# 1-Schematic_LEDmatrix.net
KiCad netlist of a schematic drawn in EasyEDA
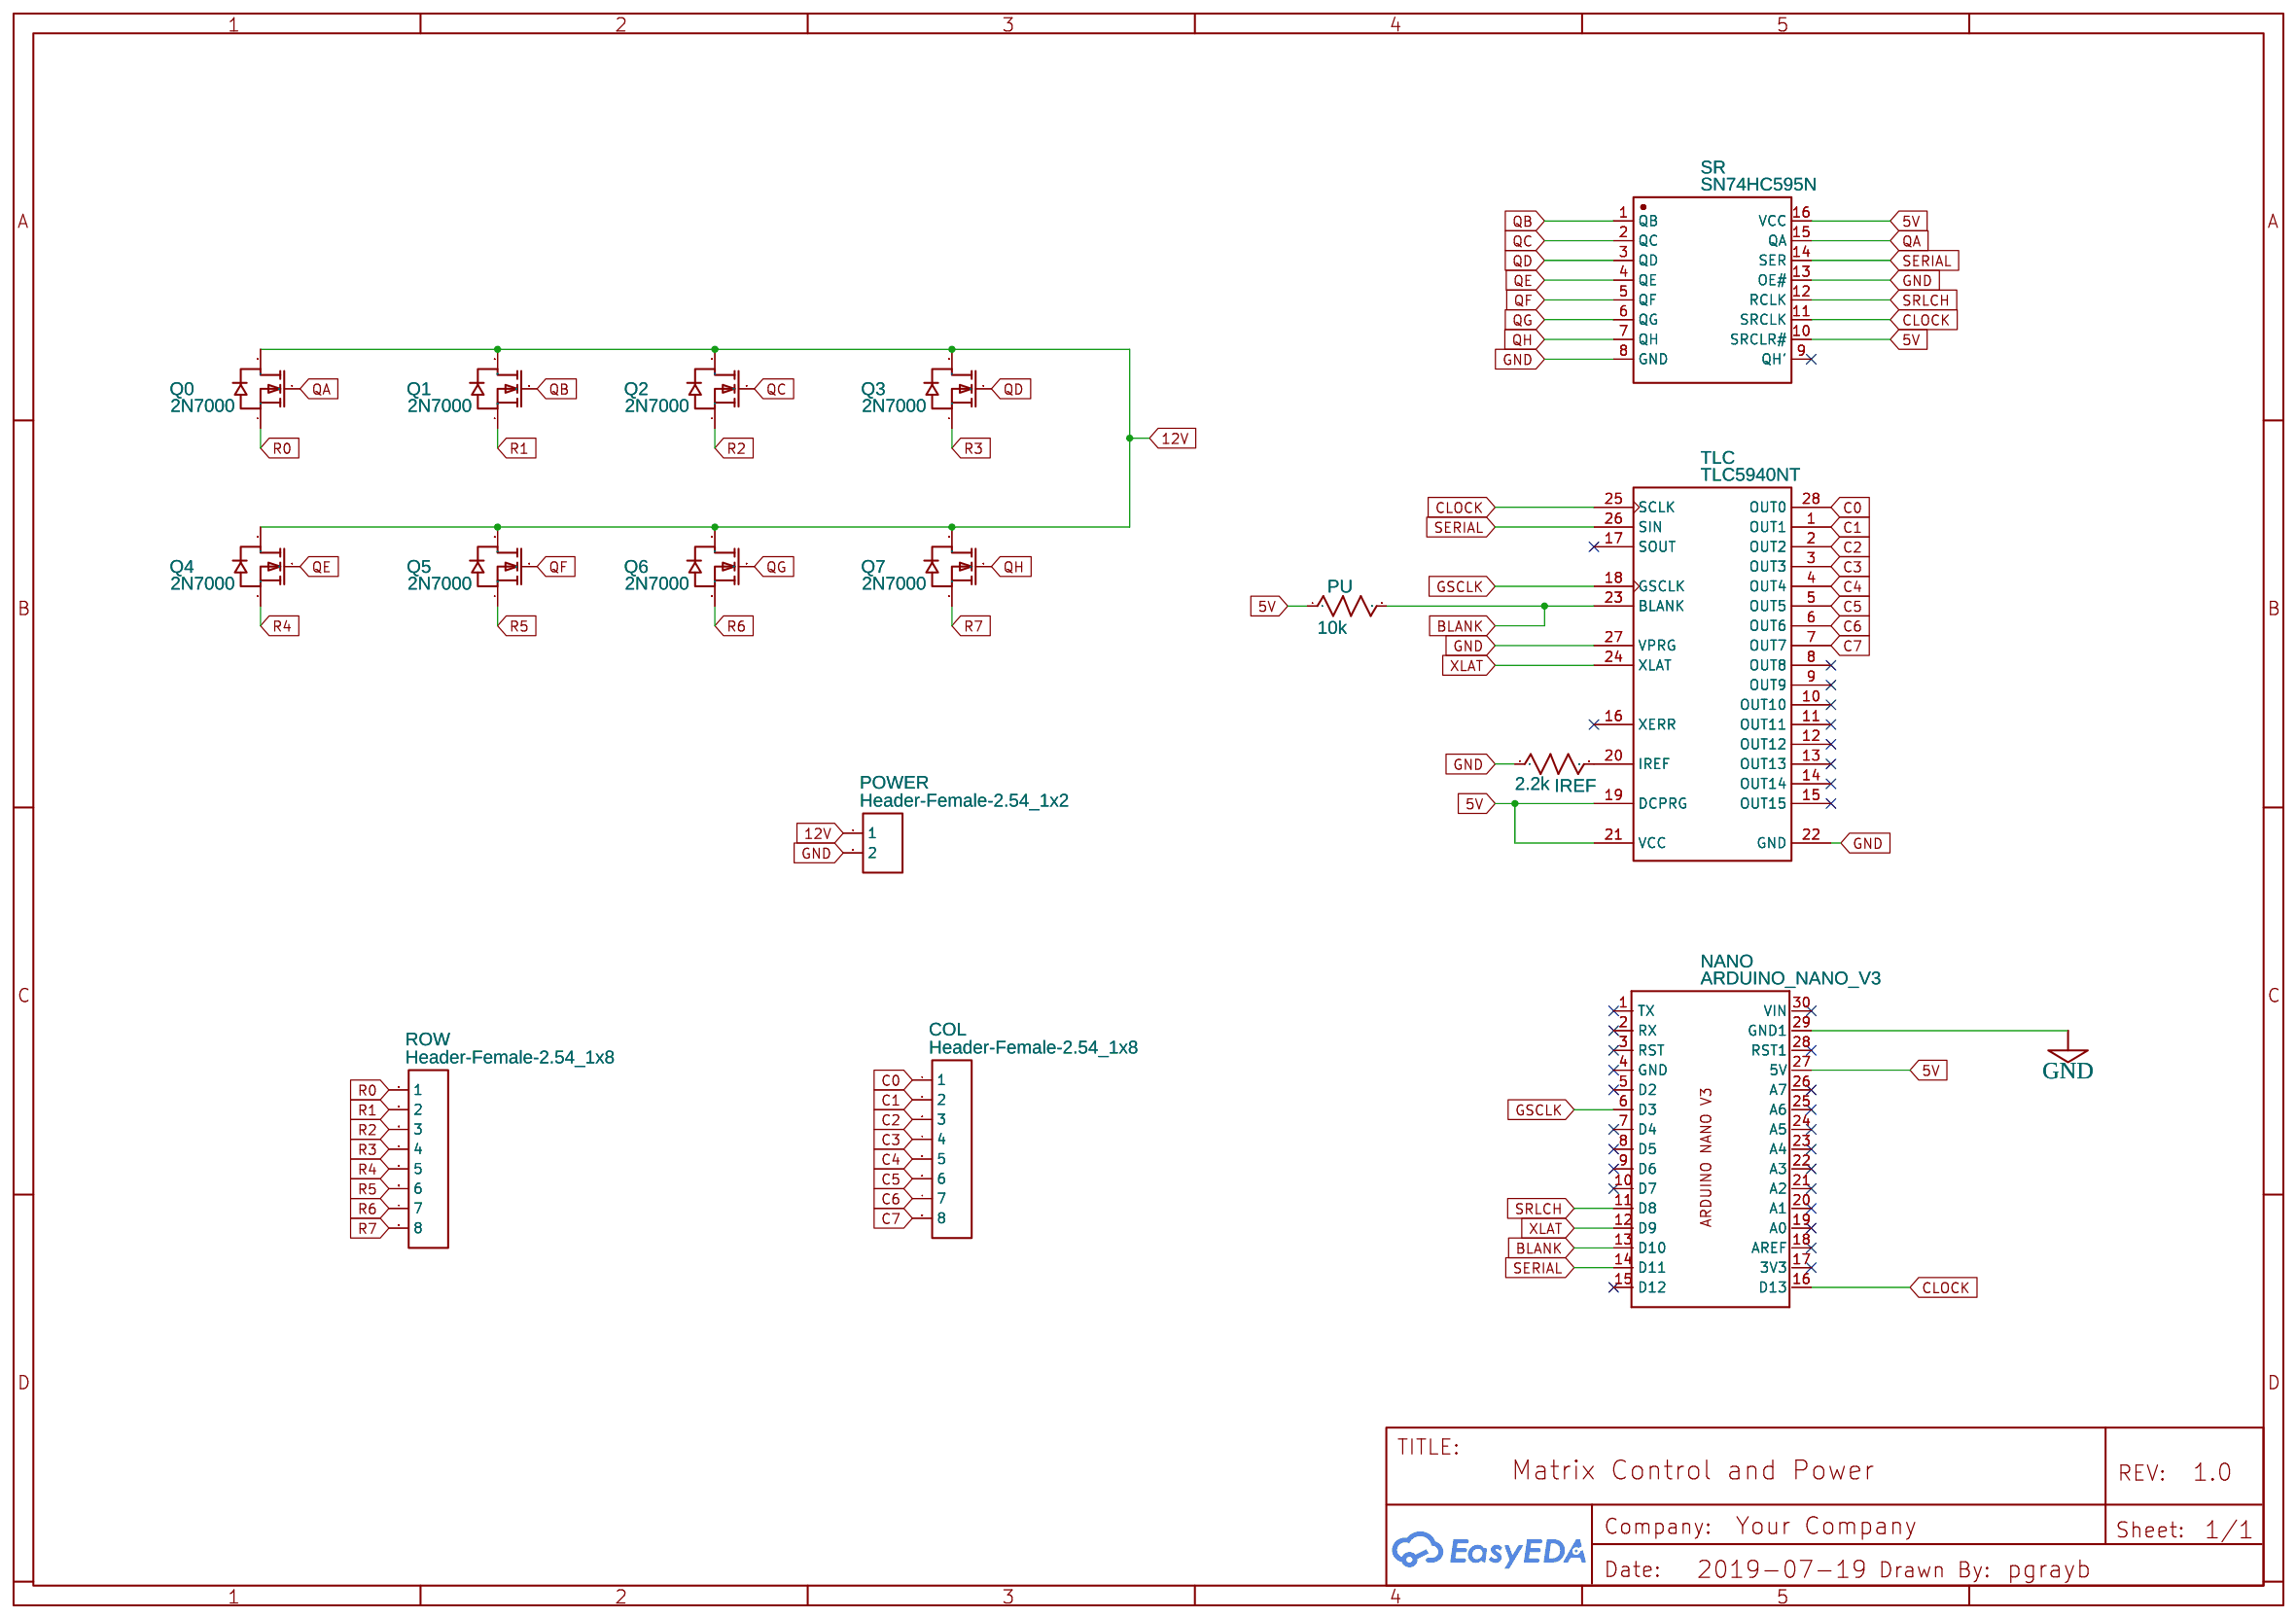
[diagram p0: schematic sheet]

(export (version "E")
  (design (tool "Eeschema 10.0.6"))
  (components
    (comp (ref "COL")
      (value "Header-Female-2.54_1x8")
      (fields
        (field (name "BOM_Manufacturer Part") "Female headerHDR1X8-2.54")
        (field (name "BOM_Supplier Part") "C27438")
      )
      (libsource (lib "") (part "Unknown_470_575"))
    )
    (comp (ref "IREF")
      (value "2.2k")
      (fields (field (name "BOM_Manufacturer Part") "?"))
      (libsource (lib "") (part "Res_AXIAL-0.3(1/8W)_US"))
    )
    (comp (ref "NANO")
      (value "ARDUINO_NANO_V3")
      (fields (field (name "BOM_Manufacturer Part") "?"))
      (libsource (lib "") (part "Unknown_860_575"))
    )
    (comp (ref "POWER")
      (value "Header-Female-2.54_1x2")
      (fields
        (field (name "BOM_Manufacturer Part") "2.54-1*2PFemale")
        (field (name "BOM_Supplier Part") "C49661")
      )
      (libsource (lib "") (part "Unknown_435_420"))
    )
    (comp (ref "PU")
      (value "10k")
      (fields (field (name "BOM_Manufacturer Part") "?"))
      (libsource (lib "") (part "Res_AXIAL-0.3(1/8W)_US_1"))
    )
    (comp (ref "Q0")
      (value "2N7000")
      (fields (field (name "BOM_Supplier Part") "C9114"))
      (libsource (lib "") (part "Unknown_130_190"))
    )
    (comp (ref "Q1")
      (value "2N7000")
      (fields (field (name "BOM_Supplier Part") "C9114"))
      (libsource (lib "") (part "Unknown_250_190"))
    )
    (comp (ref "Q2")
      (value "2N7000")
      (fields (field (name "BOM_Supplier Part") "C9114"))
      (libsource (lib "") (part "Unknown_360_190"))
    )
    (comp (ref "Q3")
      (value "2N7000")
      (fields (field (name "BOM_Supplier Part") "C9114"))
      (libsource (lib "") (part "Unknown_480_190"))
    )
    (comp (ref "Q4")
      (value "2N7000")
      (fields (field (name "BOM_Supplier Part") "C9114"))
      (libsource (lib "") (part "Unknown_130_280"))
    )
    (comp (ref "Q5")
      (value "2N7000")
      (fields (field (name "BOM_Supplier Part") "C9114"))
      (libsource (lib "") (part "Unknown_250_280"))
    )
    (comp (ref "Q6")
      (value "2N7000")
      (fields (field (name "BOM_Supplier Part") "C9114"))
      (libsource (lib "") (part "Unknown_360_280"))
    )
    (comp (ref "Q7")
      (value "2N7000")
      (fields (field (name "BOM_Supplier Part") "C9114"))
      (libsource (lib "") (part "Unknown_480_280"))
    )
    (comp (ref "ROW")
      (value "Header-Female-2.54_1x8")
      (fields
        (field (name "BOM_Manufacturer Part") "Female headerHDR1X8-2.54")
        (field (name "BOM_Supplier Part") "C27438")
      )
      (libsource (lib "") (part "Unknown_205_580"))
    )
    (comp (ref "SR")
      (value "SN74HC595N")
      (fields (field (name "BOM_Supplier Part") "C78711"))
      (libsource (lib "") (part "Unknown_860_140"))
    )
    (comp (ref "TLC")
      (value "TLC5940NT")
      (fields (field (name "BOM_Manufacturer Part") "?"))
      (libsource (lib "") (part "Unknown_860_335"))
    )
  )
  (nets
    (net (code "1") (name "5V") (class "Default")
      (node (ref "NANO") (pin "27") (pinfunction "5V_27") (pintype "bidirectional"))
      (node (ref "PU") (pin "1") (pinfunction "1_1") (pintype "unspecified"))
      (node (ref "SR") (pin "10") (pinfunction "SRCLR#_10") (pintype "unspecified"))
      (node (ref "SR") (pin "16") (pinfunction "VCC_16") (pintype "unspecified"))
      (node (ref "TLC") (pin "19") (pinfunction "DCPRG_19") (pintype "unspecified"))
      (node (ref "TLC") (pin "21") (pinfunction "VCC_21") (pintype "passive"))
    )
    (net (code "2") (name "12V") (class "Default")
      (node (ref "POWER") (pin "1") (pinfunction "1_1") (pintype "input"))
      (node (ref "Q0") (pin "3") (pinfunction "D_3") (pintype "unspecified"))
      (node (ref "Q1") (pin "3") (pinfunction "D_3") (pintype "unspecified"))
      (node (ref "Q2") (pin "3") (pinfunction "D_3") (pintype "unspecified"))
      (node (ref "Q3") (pin "3") (pinfunction "D_3") (pintype "unspecified"))
      (node (ref "Q4") (pin "3") (pinfunction "D_3") (pintype "unspecified"))
      (node (ref "Q5") (pin "3") (pinfunction "D_3") (pintype "unspecified"))
      (node (ref "Q6") (pin "3") (pinfunction "D_3") (pintype "unspecified"))
      (node (ref "Q7") (pin "3") (pinfunction "D_3") (pintype "unspecified"))
    )
    (net (code "3") (name "BLANK") (class "Default")
      (node (ref "NANO") (pin "13") (pinfunction "D10_13") (pintype "bidirectional"))
      (node (ref "PU") (pin "2") (pinfunction "2_2") (pintype "unspecified"))
      (node (ref "TLC") (pin "23") (pinfunction "BLANK_23") (pintype "unspecified"))
    )
    (net (code "4") (name "C0") (class "Default")
      (node (ref "COL") (pin "1") (pinfunction "1_1") (pintype "input"))
      (node (ref "TLC") (pin "28") (pinfunction "OUT0_28") (pintype "output"))
    )
    (net (code "5") (name "C1") (class "Default")
      (node (ref "COL") (pin "2") (pinfunction "2_2") (pintype "input"))
      (node (ref "TLC") (pin "1") (pinfunction "OUT1_1") (pintype "output"))
    )
    (net (code "6") (name "C2") (class "Default")
      (node (ref "COL") (pin "3") (pinfunction "3_3") (pintype "input"))
      (node (ref "TLC") (pin "2") (pinfunction "OUT2_2") (pintype "output"))
    )
    (net (code "7") (name "C3") (class "Default")
      (node (ref "COL") (pin "4") (pinfunction "4_4") (pintype "input"))
      (node (ref "TLC") (pin "3") (pinfunction "OUT3_3") (pintype "output"))
    )
    (net (code "8") (name "C4") (class "Default")
      (node (ref "COL") (pin "5") (pinfunction "5_5") (pintype "input"))
      (node (ref "TLC") (pin "4") (pinfunction "OUT4_4") (pintype "output"))
    )
    (net (code "9") (name "C5") (class "Default")
      (node (ref "COL") (pin "6") (pinfunction "6_6") (pintype "input"))
      (node (ref "TLC") (pin "5") (pinfunction "OUT5_5") (pintype "output"))
    )
    (net (code "10") (name "C6") (class "Default")
      (node (ref "COL") (pin "7") (pinfunction "7_7") (pintype "input"))
      (node (ref "TLC") (pin "6") (pinfunction "OUT6_6") (pintype "output"))
    )
    (net (code "11") (name "C7") (class "Default")
      (node (ref "COL") (pin "8") (pinfunction "8_8") (pintype "input"))
      (node (ref "TLC") (pin "7") (pinfunction "OUT7_7") (pintype "output"))
    )
    (net (code "12") (name "CLOCK") (class "Default")
      (node (ref "NANO") (pin "16") (pinfunction "D13_16") (pintype "bidirectional"))
      (node (ref "SR") (pin "11") (pinfunction "SRCLK_11") (pintype "unspecified"))
      (node (ref "TLC") (pin "25") (pinfunction "SCLK_25") (pintype "unspecified"))
    )
    (net (code "13") (name "GND") (class "Default")
      (node (ref "IREF") (pin "1") (pinfunction "1_1") (pintype "unspecified"))
      (node (ref "NANO") (pin "29") (pinfunction "GND1_29") (pintype "bidirectional"))
      (node (ref "POWER") (pin "2") (pinfunction "2_2") (pintype "input"))
      (node (ref "SR") (pin "13") (pinfunction "OE#_13") (pintype "unspecified"))
      (node (ref "SR") (pin "8") (pinfunction "GND_8") (pintype "unspecified"))
      (node (ref "TLC") (pin "22") (pinfunction "GND_22") (pintype "passive"))
      (node (ref "TLC") (pin "27") (pinfunction "VPRG_27") (pintype "unspecified"))
    )
    (net (code "14") (name "GSCLK") (class "Default")
      (node (ref "NANO") (pin "6") (pinfunction "D3_6") (pintype "bidirectional"))
      (node (ref "TLC") (pin "18") (pinfunction "GSCLK_18") (pintype "unspecified"))
    )
    (net (code "15") (name "Net-(TLC-IREF)") (class "Default")
      (node (ref "IREF") (pin "2") (pinfunction "2_2") (pintype "unspecified"))
      (node (ref "TLC") (pin "20") (pinfunction "IREF_20") (pintype "unspecified"))
    )
    (net (code "16") (name "QA") (class "Default")
      (node (ref "Q0") (pin "2") (pinfunction "G_2") (pintype "unspecified"))
      (node (ref "SR") (pin "15") (pinfunction "QA_15") (pintype "unspecified"))
    )
    (net (code "17") (name "QB") (class "Default")
      (node (ref "Q1") (pin "2") (pinfunction "G_2") (pintype "unspecified"))
      (node (ref "SR") (pin "1") (pinfunction "QB_1") (pintype "unspecified"))
    )
    (net (code "18") (name "QC") (class "Default")
      (node (ref "Q2") (pin "2") (pinfunction "G_2") (pintype "unspecified"))
      (node (ref "SR") (pin "2") (pinfunction "QC_2") (pintype "unspecified"))
    )
    (net (code "19") (name "QD") (class "Default")
      (node (ref "Q3") (pin "2") (pinfunction "G_2") (pintype "unspecified"))
      (node (ref "SR") (pin "3") (pinfunction "QD_3") (pintype "unspecified"))
    )
    (net (code "20") (name "QE") (class "Default")
      (node (ref "Q4") (pin "2") (pinfunction "G_2") (pintype "unspecified"))
      (node (ref "SR") (pin "4") (pinfunction "QE_4") (pintype "unspecified"))
    )
    (net (code "21") (name "QF") (class "Default")
      (node (ref "Q5") (pin "2") (pinfunction "G_2") (pintype "unspecified"))
      (node (ref "SR") (pin "5") (pinfunction "QF_5") (pintype "unspecified"))
    )
    (net (code "22") (name "QG") (class "Default")
      (node (ref "Q6") (pin "2") (pinfunction "G_2") (pintype "unspecified"))
      (node (ref "SR") (pin "6") (pinfunction "QG_6") (pintype "unspecified"))
    )
    (net (code "23") (name "QH") (class "Default")
      (node (ref "Q7") (pin "2") (pinfunction "G_2") (pintype "unspecified"))
      (node (ref "SR") (pin "7") (pinfunction "QH_7") (pintype "unspecified"))
    )
    (net (code "24") (name "R0") (class "Default")
      (node (ref "Q0") (pin "1") (pinfunction "S_1") (pintype "unspecified"))
      (node (ref "ROW") (pin "1") (pinfunction "1_1") (pintype "input"))
    )
    (net (code "25") (name "R1") (class "Default")
      (node (ref "Q1") (pin "1") (pinfunction "S_1") (pintype "unspecified"))
      (node (ref "ROW") (pin "2") (pinfunction "2_2") (pintype "input"))
    )
    (net (code "26") (name "R2") (class "Default")
      (node (ref "Q2") (pin "1") (pinfunction "S_1") (pintype "unspecified"))
      (node (ref "ROW") (pin "3") (pinfunction "3_3") (pintype "input"))
    )
    (net (code "27") (name "R3") (class "Default")
      (node (ref "Q3") (pin "1") (pinfunction "S_1") (pintype "unspecified"))
      (node (ref "ROW") (pin "4") (pinfunction "4_4") (pintype "input"))
    )
    (net (code "28") (name "R4") (class "Default")
      (node (ref "Q4") (pin "1") (pinfunction "S_1") (pintype "unspecified"))
      (node (ref "ROW") (pin "5") (pinfunction "5_5") (pintype "input"))
    )
    (net (code "29") (name "R5") (class "Default")
      (node (ref "Q5") (pin "1") (pinfunction "S_1") (pintype "unspecified"))
      (node (ref "ROW") (pin "6") (pinfunction "6_6") (pintype "input"))
    )
    (net (code "30") (name "R6") (class "Default")
      (node (ref "Q6") (pin "1") (pinfunction "S_1") (pintype "unspecified"))
      (node (ref "ROW") (pin "7") (pinfunction "7_7") (pintype "input"))
    )
    (net (code "31") (name "R7") (class "Default")
      (node (ref "Q7") (pin "1") (pinfunction "S_1") (pintype "unspecified"))
      (node (ref "ROW") (pin "8") (pinfunction "8_8") (pintype "input"))
    )
    (net (code "32") (name "SERIAL") (class "Default")
      (node (ref "NANO") (pin "14") (pinfunction "D11_14") (pintype "bidirectional"))
      (node (ref "SR") (pin "14") (pinfunction "SER_14") (pintype "unspecified"))
      (node (ref "TLC") (pin "26") (pinfunction "SIN_26") (pintype "unspecified"))
    )
    (net (code "33") (name "SRLCH") (class "Default")
      (node (ref "NANO") (pin "11") (pinfunction "D8_11") (pintype "bidirectional"))
      (node (ref "SR") (pin "12") (pinfunction "RCLK_12") (pintype "unspecified"))
    )
    (net (code "34") (name "XLAT") (class "Default")
      (node (ref "NANO") (pin "12") (pinfunction "D9_12") (pintype "bidirectional"))
      (node (ref "TLC") (pin "24") (pinfunction "XLAT_24") (pintype "unspecified"))
    )
    (net (code "35") (name "unconnected-(NANO-3V3-Pad17)") (class "Default")
      (node (ref "NANO") (pin "17") (pinfunction "3V3_17") (pintype "bidirectional+no_connect"))
    )
    (net (code "36") (name "unconnected-(NANO-A0-Pad19)") (class "Default")
      (node (ref "NANO") (pin "19") (pinfunction "A0_19") (pintype "bidirectional+no_connect"))
    )
    (net (code "37") (name "unconnected-(NANO-A1-Pad20)") (class "Default")
      (node (ref "NANO") (pin "20") (pinfunction "A1_20") (pintype "bidirectional+no_connect"))
    )
    (net (code "38") (name "unconnected-(NANO-A2-Pad21)") (class "Default")
      (node (ref "NANO") (pin "21") (pinfunction "A2_21") (pintype "bidirectional+no_connect"))
    )
    (net (code "39") (name "unconnected-(NANO-A3-Pad22)") (class "Default")
      (node (ref "NANO") (pin "22") (pinfunction "A3_22") (pintype "bidirectional+no_connect"))
    )
    (net (code "40") (name "unconnected-(NANO-A4-Pad23)") (class "Default")
      (node (ref "NANO") (pin "23") (pinfunction "A4_23") (pintype "bidirectional+no_connect"))
    )
    (net (code "41") (name "unconnected-(NANO-A5-Pad24)") (class "Default")
      (node (ref "NANO") (pin "24") (pinfunction "A5_24") (pintype "bidirectional+no_connect"))
    )
    (net (code "42") (name "unconnected-(NANO-A6-Pad25)") (class "Default")
      (node (ref "NANO") (pin "25") (pinfunction "A6_25") (pintype "bidirectional+no_connect"))
    )
    (net (code "43") (name "unconnected-(NANO-A7-Pad26)") (class "Default")
      (node (ref "NANO") (pin "26") (pinfunction "A7_26") (pintype "bidirectional+no_connect"))
    )
    (net (code "44") (name "unconnected-(NANO-AREF-Pad18)") (class "Default")
      (node (ref "NANO") (pin "18") (pinfunction "AREF_18") (pintype "bidirectional+no_connect"))
    )
    (net (code "45") (name "unconnected-(NANO-D2-Pad5)") (class "Default")
      (node (ref "NANO") (pin "5") (pinfunction "D2_5") (pintype "bidirectional+no_connect"))
    )
    (net (code "46") (name "unconnected-(NANO-D4-Pad7)") (class "Default")
      (node (ref "NANO") (pin "7") (pinfunction "D4_7") (pintype "bidirectional+no_connect"))
    )
    (net (code "47") (name "unconnected-(NANO-D5-Pad8)") (class "Default")
      (node (ref "NANO") (pin "8") (pinfunction "D5_8") (pintype "bidirectional+no_connect"))
    )
    (net (code "48") (name "unconnected-(NANO-D6-Pad9)") (class "Default")
      (node (ref "NANO") (pin "9") (pinfunction "D6_9") (pintype "bidirectional+no_connect"))
    )
    (net (code "49") (name "unconnected-(NANO-D7-Pad10)") (class "Default")
      (node (ref "NANO") (pin "10") (pinfunction "D7_10") (pintype "bidirectional+no_connect"))
    )
    (net (code "50") (name "unconnected-(NANO-D12-Pad15)") (class "Default")
      (node (ref "NANO") (pin "15") (pinfunction "D12_15") (pintype "bidirectional+no_connect"))
    )
    (net (code "51") (name "unconnected-(NANO-GND-Pad4)") (class "Default")
      (node (ref "NANO") (pin "4") (pinfunction "GND_4") (pintype "bidirectional+no_connect"))
    )
    (net (code "52") (name "unconnected-(NANO-RST-Pad3)") (class "Default")
      (node (ref "NANO") (pin "3") (pinfunction "RST_3") (pintype "bidirectional+no_connect"))
    )
    (net (code "53") (name "unconnected-(NANO-RST1-Pad28)") (class "Default")
      (node (ref "NANO") (pin "28") (pinfunction "RST1_28") (pintype "bidirectional+no_connect"))
    )
    (net (code "54") (name "unconnected-(NANO-RX-Pad2)") (class "Default")
      (node (ref "NANO") (pin "2") (pinfunction "RX_2") (pintype "bidirectional+no_connect"))
    )
    (net (code "55") (name "unconnected-(NANO-TX-Pad1)") (class "Default")
      (node (ref "NANO") (pin "1") (pinfunction "TX_1") (pintype "bidirectional+no_connect"))
    )
    (net (code "56") (name "unconnected-(NANO-VIN-Pad30)") (class "Default")
      (node (ref "NANO") (pin "30") (pinfunction "VIN_30") (pintype "bidirectional+no_connect"))
    )
    (net (code "57") (name "unconnected-(SR-QH'-Pad9)") (class "Default")
      (node (ref "SR") (pin "9") (pinfunction "QH'_9") (pintype "unspecified+no_connect"))
    )
    (net (code "58") (name "unconnected-(TLC-OUT8-Pad8)") (class "Default")
      (node (ref "TLC") (pin "8") (pinfunction "OUT8_8") (pintype "output+no_connect"))
    )
    (net (code "59") (name "unconnected-(TLC-OUT9-Pad9)") (class "Default")
      (node (ref "TLC") (pin "9") (pinfunction "OUT9_9") (pintype "output+no_connect"))
    )
    (net (code "60") (name "unconnected-(TLC-OUT10-Pad10)") (class "Default")
      (node (ref "TLC") (pin "10") (pinfunction "OUT10_10") (pintype "output+no_connect"))
    )
    (net (code "61") (name "unconnected-(TLC-OUT11-Pad11)") (class "Default")
      (node (ref "TLC") (pin "11") (pinfunction "OUT11_11") (pintype "output+no_connect"))
    )
    (net (code "62") (name "unconnected-(TLC-OUT12-Pad12)") (class "Default")
      (node (ref "TLC") (pin "12") (pinfunction "OUT12_12") (pintype "output+no_connect"))
    )
    (net (code "63") (name "unconnected-(TLC-OUT13-Pad13)") (class "Default")
      (node (ref "TLC") (pin "13") (pinfunction "OUT13_13") (pintype "output+no_connect"))
    )
    (net (code "64") (name "unconnected-(TLC-OUT14-Pad14)") (class "Default")
      (node (ref "TLC") (pin "14") (pinfunction "OUT14_14") (pintype "output+no_connect"))
    )
    (net (code "65") (name "unconnected-(TLC-OUT15-Pad15)") (class "Default")
      (node (ref "TLC") (pin "15") (pinfunction "OUT15_15") (pintype "output+no_connect"))
    )
    (net (code "66") (name "unconnected-(TLC-SOUT-Pad17)") (class "Default")
      (node (ref "TLC") (pin "17") (pinfunction "SOUT_17") (pintype "output+no_connect"))
    )
    (net (code "67") (name "unconnected-(TLC-XERR-Pad16)") (class "Default")
      (node (ref "TLC") (pin "16") (pinfunction "XERR_16") (pintype "unspecified+no_connect"))
    )
  )
)
